# F405ADC_plata.net
KiCad netlist of a schematic drawn in Altium Designer
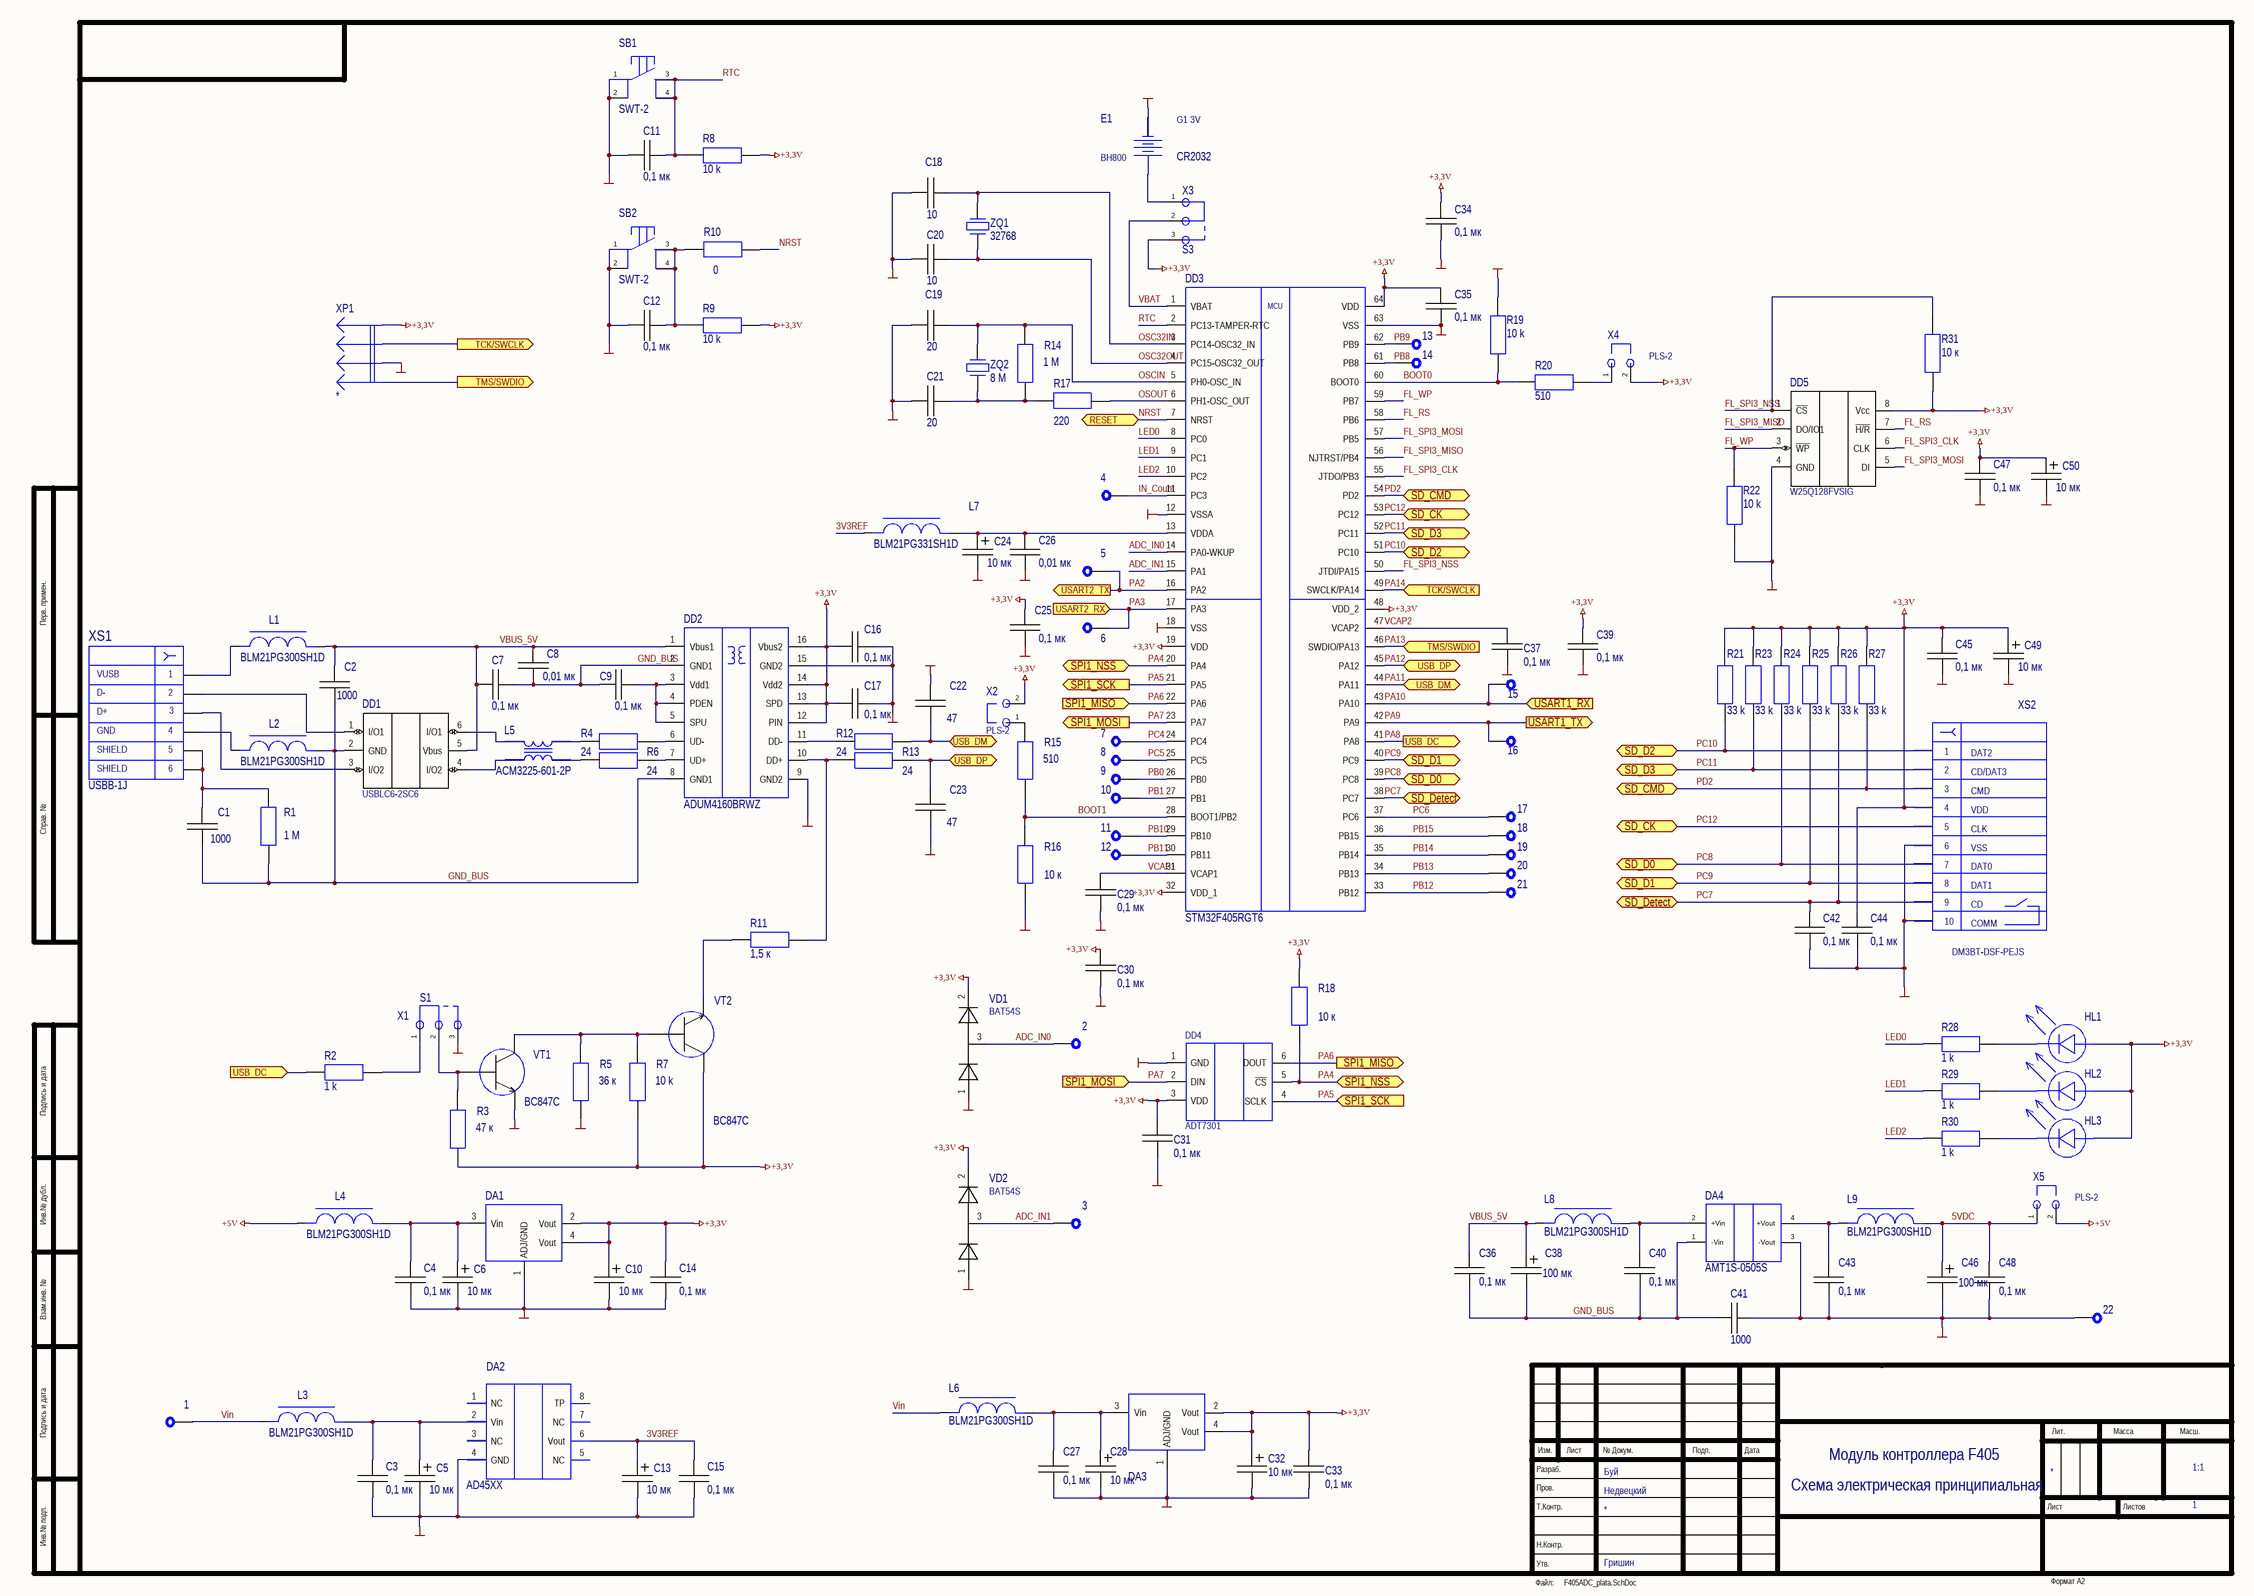
[diagram p0: F405ADC_plata.SchDoc]

(export (version "E")
  (design (tool "Eeschema 10.0.6"))
  (components
    (comp (ref "1")
      (value "PIN")
      (footprint "Hole")
      (description "PIN, hole")
      (libsource (lib "Connectors") (part "PIN"))
    )
    (comp (ref "2")
      (value "PIN")
      (footprint "Hole")
      (description "PIN, hole")
      (libsource (lib "Connectors") (part "PIN"))
    )
    (comp (ref "3")
      (value "PIN")
      (footprint "Hole")
      (description "PIN, hole")
      (libsource (lib "Connectors") (part "PIN"))
    )
    (comp (ref "4")
      (value "PIN")
      (footprint "Hole")
      (description "PIN, hole")
      (libsource (lib "Connectors") (part "PIN"))
    )
    (comp (ref "5")
      (value "PIN")
      (footprint "Hole")
      (description "PIN, hole")
      (libsource (lib "Connectors") (part "PIN"))
    )
    (comp (ref "6")
      (value "PIN")
      (footprint "Hole")
      (description "PIN, hole")
      (libsource (lib "Connectors") (part "PIN"))
    )
    (comp (ref "7")
      (value "PIN")
      (footprint "Hole")
      (description "PIN, hole")
      (libsource (lib "Connectors") (part "PIN"))
    )
    (comp (ref "8")
      (value "PIN")
      (footprint "Hole")
      (description "PIN, hole")
      (libsource (lib "Connectors") (part "PIN"))
    )
    (comp (ref "9")
      (value "PIN")
      (footprint "Hole")
      (description "PIN, hole")
      (libsource (lib "Connectors") (part "PIN"))
    )
    (comp (ref "10")
      (value "PIN")
      (footprint "Hole")
      (description "PIN, hole")
      (libsource (lib "Connectors") (part "PIN"))
    )
    (comp (ref "11")
      (value "PIN")
      (footprint "Hole")
      (description "PIN, hole")
      (libsource (lib "Connectors") (part "PIN"))
    )
    (comp (ref "12")
      (value "PIN")
      (footprint "Hole")
      (description "PIN, hole")
      (libsource (lib "Connectors") (part "PIN"))
    )
    (comp (ref "13")
      (value "PIN")
      (footprint "Hole")
      (description "PIN, hole")
      (libsource (lib "Connectors") (part "PIN"))
    )
    (comp (ref "14")
      (value "PIN")
      (footprint "Hole")
      (description "PIN, hole")
      (libsource (lib "Connectors") (part "PIN"))
    )
    (comp (ref "15")
      (value "PIN")
      (footprint "Hole")
      (description "PIN, hole")
      (libsource (lib "Connectors") (part "PIN"))
    )
    (comp (ref "16")
      (value "PIN")
      (footprint "Hole")
      (description "PIN, hole")
      (libsource (lib "Connectors") (part "PIN"))
    )
    (comp (ref "17")
      (value "PIN")
      (footprint "Hole")
      (description "PIN, hole")
      (libsource (lib "Connectors") (part "PIN"))
    )
    (comp (ref "18")
      (value "PIN")
      (footprint "Hole")
      (description "PIN, hole")
      (libsource (lib "Connectors") (part "PIN"))
    )
    (comp (ref "19")
      (value "PIN")
      (footprint "Hole")
      (description "PIN, hole")
      (libsource (lib "Connectors") (part "PIN"))
    )
    (comp (ref "20")
      (value "PIN")
      (footprint "Hole")
      (description "PIN, hole")
      (libsource (lib "Connectors") (part "PIN"))
    )
    (comp (ref "21")
      (value "PIN")
      (footprint "Hole")
      (description "PIN, hole")
      (libsource (lib "Connectors") (part "PIN"))
    )
    (comp (ref "22")
      (value "PIN")
      (footprint "Hole")
      (description "PIN, hole")
      (libsource (lib "Connectors") (part "PIN"))
    )
    (comp (ref "C1")
      (value "1000")
      (footprint "C0805")
      (description "Capasitor")
      (fields (field (name "PART NUMBER") "C"))
      (libsource (lib "RLC_GOST") (part "C"))
    )
    (comp (ref "C2")
      (value "1000")
      (footprint "C0805")
      (description "Capasitor")
      (libsource (lib "RLC_GOST") (part "C"))
    )
    (comp (ref "C3")
      (value "0,1 мк")
      (footprint "C0805")
      (description "Capasitor")
      (fields (field (name "PART NUMBER") "C"))
      (libsource (lib "RLC_GOST") (part "C"))
    )
    (comp (ref "C4")
      (value "0,1 мк")
      (footprint "C0805")
      (description "Capasitor")
      (fields (field (name "PART NUMBER") "C"))
      (libsource (lib "RLC_GOST") (part "C"))
    )
    (comp (ref "C5")
      (value "10 мк")
      (footprint "3216")
      (description "Capasitor_polar")
      (fields (field (name "PART NUMBER") "CapPol"))
      (libsource (lib "RLC_GOST") (part "CapPol"))
    )
    (comp (ref "C6")
      (value "10 мк")
      (footprint "3216")
      (description "Capasitor_polar")
      (fields (field (name "PART NUMBER") "CapPol"))
      (libsource (lib "RLC_GOST") (part "CapPol"))
    )
    (comp (ref "C7")
      (value "0,1 мк")
      (footprint "C0805")
      (description "Capasitor")
      (fields (field (name "PART NUMBER") "C"))
      (libsource (lib "RLC_GOST") (part "C"))
    )
    (comp (ref "C8")
      (value "0,01 мк")
      (footprint "C0805")
      (description "Capasitor")
      (fields (field (name "PART NUMBER") "C"))
      (libsource (lib "RLC_GOST") (part "C"))
    )
    (comp (ref "C9")
      (value "0,1 мк")
      (footprint "C0805")
      (description "Capasitor")
      (fields (field (name "PART NUMBER") "C"))
      (libsource (lib "RLC_GOST") (part "C"))
    )
    (comp (ref "C10")
      (value "10 мк")
      (footprint "3216")
      (description "Capasitor_polar")
      (fields (field (name "PART NUMBER") "CapPol"))
      (libsource (lib "RLC_GOST") (part "CapPol"))
    )
    (comp (ref "C11")
      (value "0,1 мк")
      (footprint "C0805")
      (description "Capasitor")
      (libsource (lib "RLC_GOST") (part "C"))
    )
    (comp (ref "C12")
      (value "0,1 мк")
      (footprint "C0805")
      (description "Capasitor")
      (libsource (lib "RLC_GOST") (part "C"))
    )
    (comp (ref "C13")
      (value "10 мк")
      (footprint "3216")
      (description "Capasitor_polar")
      (fields (field (name "PART NUMBER") "CapPol"))
      (libsource (lib "RLC_GOST") (part "CapPol"))
    )
    (comp (ref "C14")
      (value "0,1 мк")
      (footprint "C0805")
      (description "Capasitor")
      (fields (field (name "PART NUMBER") "C"))
      (libsource (lib "RLC_GOST") (part "C"))
    )
    (comp (ref "C15")
      (value "0,1 мк")
      (footprint "C0805")
      (description "Capasitor")
      (fields (field (name "PART NUMBER") "C"))
      (libsource (lib "RLC_GOST") (part "C"))
    )
    (comp (ref "C16")
      (value "0,1 мк")
      (footprint "C0805")
      (description "Capasitor")
      (fields (field (name "PART NUMBER") "C"))
      (libsource (lib "RLC_GOST") (part "C"))
    )
    (comp (ref "C17")
      (value "0,1 мк")
      (footprint "C0805")
      (description "Capasitor")
      (fields (field (name "PART NUMBER") "C"))
      (libsource (lib "RLC_GOST") (part "C"))
    )
    (comp (ref "C18")
      (value "10")
      (footprint "CAPC1608X05N")
      (description "Capasitor")
      (libsource (lib "RLC_GOST") (part "C"))
    )
    (comp (ref "C19")
      (value "20")
      (footprint "CAPC1608X05N")
      (description "Capasitor")
      (libsource (lib "RLC_GOST") (part "C"))
    )
    (comp (ref "C20")
      (value "10")
      (footprint "CAPC1608X05N")
      (description "Capasitor")
      (libsource (lib "RLC_GOST") (part "C"))
    )
    (comp (ref "C21")
      (value "20")
      (footprint "CAPC1608X05N")
      (description "Capasitor")
      (libsource (lib "RLC_GOST") (part "C"))
    )
    (comp (ref "C22")
      (value "47")
      (footprint "C0805")
      (description "Capasitor")
      (fields (field (name "PART NUMBER") "C"))
      (libsource (lib "RLC_GOST") (part "C"))
    )
    (comp (ref "C23")
      (value "47")
      (footprint "C0805")
      (description "Capasitor")
      (fields (field (name "PART NUMBER") "C"))
      (libsource (lib "RLC_GOST") (part "C"))
    )
    (comp (ref "C24")
      (value "10 мк")
      (footprint "3216")
      (description "Capasitor_polar")
      (fields (field (name "PART NUMBER") "CapPol"))
      (libsource (lib "RLC_GOST") (part "CapPol"))
    )
    (comp (ref "C25")
      (value "0,1 мк")
      (footprint "C0805")
      (description "Capasitor")
      (fields (field (name "PART NUMBER") "C"))
      (libsource (lib "RLC_GOST") (part "C"))
    )
    (comp (ref "C26")
      (value "0,01 мк")
      (footprint "C0805")
      (description "Capasitor")
      (fields (field (name "PART NUMBER") "C"))
      (libsource (lib "RLC_GOST") (part "C"))
    )
    (comp (ref "C27")
      (value "0,1 мк")
      (footprint "C0805")
      (description "Capasitor")
      (fields (field (name "PART NUMBER") "C"))
      (libsource (lib "RLC_GOST") (part "C"))
    )
    (comp (ref "C28")
      (value "10 мк")
      (footprint "3216")
      (description "Capasitor_polar")
      (fields (field (name "PART NUMBER") "CapPol"))
      (libsource (lib "RLC_GOST") (part "CapPol"))
    )
    (comp (ref "C29")
      (value "0,1 мк")
      (footprint "C0805")
      (description "Capasitor")
      (fields (field (name "PART NUMBER") "C"))
      (libsource (lib "RLC_GOST") (part "C"))
    )
    (comp (ref "C30")
      (value "0,1 мк")
      (footprint "C0805")
      (description "Capasitor")
      (fields (field (name "PART NUMBER") "C"))
      (libsource (lib "RLC_GOST") (part "C"))
    )
    (comp (ref "C31")
      (value "0,1 мк")
      (footprint "C0805")
      (description "Capasitor")
      (fields (field (name "PART NUMBER") "C"))
      (libsource (lib "RLC_GOST") (part "C"))
    )
    (comp (ref "C32")
      (value "10 мк")
      (footprint "3216")
      (description "Capasitor_polar")
      (fields (field (name "PART NUMBER") "CapPol"))
      (libsource (lib "RLC_GOST") (part "CapPol"))
    )
    (comp (ref "C33")
      (value "0,1 мк")
      (footprint "C0805")
      (description "Capasitor")
      (fields (field (name "PART NUMBER") "C"))
      (libsource (lib "RLC_GOST") (part "C"))
    )
    (comp (ref "C34")
      (value "0,1 мк")
      (footprint "C0805")
      (description "Capasitor")
      (fields (field (name "PART NUMBER") "C"))
      (libsource (lib "RLC_GOST") (part "C"))
    )
    (comp (ref "C35")
      (value "0,1 мк")
      (footprint "C0805")
      (description "Capasitor")
      (fields (field (name "PART NUMBER") "C"))
      (libsource (lib "RLC_GOST") (part "C"))
    )
    (comp (ref "C36")
      (value "0,1 мк")
      (footprint "C0805")
      (description "Capasitor")
      (fields (field (name "PART NUMBER") "C"))
      (libsource (lib "RLC_GOST") (part "C"))
    )
    (comp (ref "C37")
      (value "0,1 мк")
      (footprint "RC0805-2.2")
      (description "Capasitor")
      (fields (field (name "PART NUMBER") "C"))
      (libsource (lib "RLC_GOST") (part "C"))
    )
    (comp (ref "C38")
      (value "100 мк")
      (footprint "X-7343-43")
      (description "Capasitor_polar")
      (libsource (lib "") (part "CapPol_1"))
    )
    (comp (ref "C39")
      (value "0,1 мк")
      (footprint "C0805")
      (description "Capasitor")
      (fields (field (name "PART NUMBER") "C"))
      (libsource (lib "RLC_GOST") (part "C"))
    )
    (comp (ref "C40")
      (value "0,1 мк")
      (footprint "C0805")
      (description "Capasitor")
      (fields (field (name "PART NUMBER") "C"))
      (libsource (lib "RLC_GOST") (part "C"))
    )
    (comp (ref "C41")
      (value "1000")
      (footprint "KVR")
      (description "Capasitor")
      (libsource (lib "RLC_GOST") (part "C"))
    )
    (comp (ref "C42")
      (value "0,1 мк")
      (footprint "C0805")
      (description "Capasitor")
      (fields (field (name "PART NUMBER") "C"))
      (libsource (lib "RLC_GOST") (part "C"))
    )
    (comp (ref "C43")
      (value "0,1 мк")
      (footprint "C0805")
      (description "Capasitor")
      (fields (field (name "PART NUMBER") "C"))
      (libsource (lib "RLC_GOST") (part "C"))
    )
    (comp (ref "C44")
      (value "0,1 мк")
      (footprint "C0805")
      (description "Capasitor")
      (fields (field (name "PART NUMBER") "C"))
      (libsource (lib "RLC_GOST") (part "C"))
    )
    (comp (ref "C45")
      (value "0,1 мк")
      (footprint "C0805")
      (description "Capasitor")
      (fields (field (name "PART NUMBER") "C"))
      (libsource (lib "RLC_GOST") (part "C"))
    )
    (comp (ref "C46")
      (value "100 мк")
      (footprint "X-7343-43")
      (description "Capasitor_polar")
      (libsource (lib "") (part "CapPol_1"))
    )
    (comp (ref "C47")
      (value "0,1 мк")
      (footprint "C0805")
      (description "Capasitor")
      (fields (field (name "PART NUMBER") "C"))
      (libsource (lib "RLC_GOST") (part "C"))
    )
    (comp (ref "C48")
      (value "0,1 мк")
      (footprint "C0805")
      (description "Capasitor")
      (fields (field (name "PART NUMBER") "C"))
      (libsource (lib "RLC_GOST") (part "C"))
    )
    (comp (ref "C49")
      (value "10 мк")
      (footprint "3216")
      (description "Capasitor_polar")
      (fields (field (name "PART NUMBER") "CapPol"))
      (libsource (lib "RLC_GOST") (part "CapPol"))
    )
    (comp (ref "C50")
      (value "10 мк")
      (footprint "3216")
      (description "Capasitor_polar")
      (fields (field (name "PART NUMBER") "CapPol"))
      (libsource (lib "RLC_GOST") (part "CapPol"))
    )
    (comp (ref "DA1")
      (value "LM1117")
      (footprint "SOT223")
      (description "Positive voltage regulators")
      (fields (field (name "MANUFACTURER") "National Semiconductor"))
      (libsource (lib "Stabil") (part "LM1117"))
    )
    (comp (ref "DA2")
      (value "AD45XX")
      (footprint "SO8")
      (description "Ultralow Noise, High Accuracy  Voltage References")
      (fields (field (name "MANUFACTURER") "Analog Devices"))
      (libsource (lib "REF") (part "AD45XX"))
    )
    (comp (ref "DA3")
      (value "LM1117")
      (footprint "SOT223")
      (description "Positive voltage regulators")
      (fields (field (name "MANUFACTURER") "National Semiconductor"))
      (libsource (lib "Stabil") (part "LM1117"))
    )
    (comp (ref "DA4")
      (value "AMT1S-0505S")
      (footprint "HOLE_4")
      (libsource (lib "ConverterDC") (part "AMT1S-0505S"))
    )
    (comp (ref "DD1")
      (value "USBLC6-2SC6")
      (footprint "SOT23-6L")
      (description "ESD PROTECTION")
      (fields (field (name "MANUFACTURER") "STMicroelectronics"))
      (libsource (lib "Diod") (part "USBLC6"))
    )
    (comp (ref "DD2")
      (value "ADUM4160BRWZ")
      (footprint "RW-16")
      (libsource (lib "IsolatedCircuit") (part "ADUM4160"))
    )
    (comp (ref "DD3")
      (value "STM32F405RGT6")
      (footprint "LQFP64_M")
      (libsource (lib "STM32") (part "STM32F405RGT6"))
    )
    (comp (ref "DD4")
      (value "ADT7301")
      (footprint "SOT23-6")
      (description "Temperature sensor")
      (libsource (lib "temp_sensor") (part "ADT7301"))
    )
    (comp (ref "DD5")
      (value "W25Q128FVSIG")
      (footprint "SOIC127P790X100-8N")
      (description "Flash")
      (libsource (lib "Communication transceiver") (part "W25Q128FVSIG"))
    )
    (comp (ref "E1")
      (value "BH800")
      (footprint "BATTERY_20mm")
      (fields (field (name "ALTIUM_VALUE") "CR2032") (field (name "G") "G1 3V"))
      (libsource (lib "Connectors") (part "BH800"))
    )
    (comp (ref "HL1")
      (value "REC-T1608UYC-B1-6")
      (footprint "C0805")
      (description "HL")
      (libsource (lib "Diodes") (part "HLSMD"))
    )
    (comp (ref "HL2")
      (value "REC-T1608UYC-B1-6")
      (footprint "C0805")
      (description "HL")
      (libsource (lib "Diodes") (part "HLSMD"))
    )
    (comp (ref "HL3")
      (value "REC-T1608UYC-B1-6")
      (footprint "C0805")
      (description "HL")
      (libsource (lib "Diodes") (part "HLSMD"))
    )
    (comp (ref "L1")
      (value "BLM21PG300SH1D")
      (footprint "C0805")
      (description "Ferrite bead")
      (libsource (lib "RLC_GOST") (part "B"))
    )
    (comp (ref "L2")
      (value "BLM21PG300SH1D")
      (footprint "C0805")
      (description "Ferrite bead")
      (libsource (lib "RLC_GOST") (part "B"))
    )
    (comp (ref "L3")
      (value "BLM21PG300SH1D")
      (footprint "C0805")
      (description "Ferrite bead")
      (libsource (lib "RLC_GOST") (part "B"))
    )
    (comp (ref "L4")
      (value "BLM21PG300SH1D")
      (footprint "C0805")
      (description "Ferrite bead")
      (libsource (lib "RLC_GOST") (part "B"))
    )
    (comp (ref "L5")
      (value "ACM3225-601-2P")
      (footprint "ACM3225")
      (libsource (lib "RLC_GOST") (part "ACM3225-601-2P"))
    )
    (comp (ref "L6")
      (value "BLM21PG300SH1D")
      (footprint "C0805")
      (description "Ferrite bead")
      (libsource (lib "RLC_GOST") (part "B"))
    )
    (comp (ref "L7")
      (value "BLM21PG331SH1D")
      (footprint "C0805")
      (description "Ferrite bead")
      (libsource (lib "RLC_GOST") (part "B"))
    )
    (comp (ref "L8")
      (value "BLM21PG300SH1D")
      (footprint "C0805")
      (description "Ferrite bead")
      (libsource (lib "RLC_GOST") (part "B"))
    )
    (comp (ref "L9")
      (value "BLM21PG300SH1D")
      (footprint "C0805")
      (description "Ferrite bead")
      (libsource (lib "RLC_GOST") (part "B"))
    )
    (comp (ref "R1")
      (value "1 M")
      (footprint "RC0805-2")
      (description "Resistor,2 Pin")
      (libsource (lib "RLC_GOST") (part "R_Gost"))
    )
    (comp (ref "R2")
      (value "1 k")
      (footprint "RC0805-2")
      (description "Resistor,2 Pin")
      (libsource (lib "RLC_GOST") (part "R_Gost"))
    )
    (comp (ref "R3")
      (value "47 к")
      (footprint "RC0805-2")
      (description "Resistor,2 Pin")
      (libsource (lib "RLC_GOST") (part "R_Gost"))
    )
    (comp (ref "R4")
      (value "24")
      (footprint "RC0805-2")
      (description "Resistor,2 Pin")
      (libsource (lib "RLC_GOST") (part "R_Gost"))
    )
    (comp (ref "R5")
      (value "36 к")
      (footprint "RC0805-2")
      (description "Resistor,2 Pin")
      (libsource (lib "RLC_GOST") (part "R_Gost"))
    )
    (comp (ref "R6")
      (value "24")
      (footprint "RC0805-2")
      (description "Resistor,2 Pin")
      (libsource (lib "RLC_GOST") (part "R_Gost"))
    )
    (comp (ref "R7")
      (value "10 k")
      (footprint "RC0805-2")
      (description "Resistor,2 Pin")
      (libsource (lib "RLC_GOST") (part "R_Gost"))
    )
    (comp (ref "R8")
      (value "10 k")
      (footprint "RC0805-2")
      (description "Resistor,2 Pin")
      (libsource (lib "RLC_GOST") (part "R_Gost"))
    )
    (comp (ref "R9")
      (value "10 k")
      (footprint "RC0805-2")
      (description "Resistor,2 Pin")
      (libsource (lib "RLC_GOST") (part "R_Gost"))
    )
    (comp (ref "R10")
      (value "0")
      (footprint "RC0805-2")
      (description "Resistor,2 Pin")
      (libsource (lib "RLC_GOST") (part "R_Gost"))
    )
    (comp (ref "R11")
      (value "1,5 к")
      (footprint "RC0805-2")
      (description "Resistor,2 Pin")
      (libsource (lib "RLC_GOST") (part "R_Gost"))
    )
    (comp (ref "R12")
      (value "24")
      (footprint "RC0805-2")
      (description "Resistor,2 Pin")
      (libsource (lib "RLC_GOST") (part "R_Gost"))
    )
    (comp (ref "R13")
      (value "24")
      (footprint "RC0805-2")
      (description "Resistor,2 Pin")
      (libsource (lib "RLC_GOST") (part "R_Gost"))
    )
    (comp (ref "R14")
      (value "1 М")
      (footprint "CAPC1608X05N")
      (description "Resistor,2 Pin")
      (libsource (lib "RLC_GOST") (part "R_Gost"))
    )
    (comp (ref "R15")
      (value "510")
      (footprint "RC0805-2")
      (description "Resistor,2 Pin")
      (libsource (lib "RLC_GOST") (part "R_Gost"))
    )
    (comp (ref "R16")
      (value "10 к")
      (footprint "RC0805-2")
      (description "Resistor,2 Pin")
      (libsource (lib "RLC_GOST") (part "R_Gost"))
    )
    (comp (ref "R17")
      (value "220")
      (footprint "CAPC1608X05N")
      (description "Resistor,2 Pin")
      (libsource (lib "RLC_GOST") (part "R_Gost"))
    )
    (comp (ref "R18")
      (value "10 к")
      (footprint "RC0805-2")
      (description "Resistor,2 Pin")
      (libsource (lib "RLC_GOST") (part "R_Gost"))
    )
    (comp (ref "R19")
      (value "10 k")
      (footprint "RC0805-2.2")
      (description "Resistor,2 Pin")
      (libsource (lib "RLC_GOST") (part "R_Gost"))
    )
    (comp (ref "R20")
      (value "510")
      (footprint "RC0805-2.2")
      (description "Resistor,2 Pin")
      (libsource (lib "RLC_GOST") (part "R_Gost"))
    )
    (comp (ref "R21")
      (value "33 k")
      (footprint "RC0805-2")
      (description "Resistor,2 Pin")
      (libsource (lib "RLC_GOST") (part "R_Gost"))
    )
    (comp (ref "R22")
      (value "10 k")
      (footprint "RC0805-2")
      (description "Resistor,2 Pin")
      (libsource (lib "RLC_GOST") (part "R_Gost"))
    )
    (comp (ref "R23")
      (value "33 k")
      (footprint "RC0805-2")
      (description "Resistor,2 Pin")
      (libsource (lib "RLC_GOST") (part "R_Gost"))
    )
    (comp (ref "R24")
      (value "33 k")
      (footprint "RC0805-2")
      (description "Resistor,2 Pin")
      (libsource (lib "RLC_GOST") (part "R_Gost"))
    )
    (comp (ref "R25")
      (value "33 k")
      (footprint "RC0805-2")
      (description "Resistor,2 Pin")
      (libsource (lib "RLC_GOST") (part "R_Gost"))
    )
    (comp (ref "R26")
      (value "33 k")
      (footprint "RC0805-2")
      (description "Resistor,2 Pin")
      (libsource (lib "RLC_GOST") (part "R_Gost"))
    )
    (comp (ref "R27")
      (value "33 k")
      (footprint "RC0805-2")
      (description "Resistor,2 Pin")
      (libsource (lib "RLC_GOST") (part "R_Gost"))
    )
    (comp (ref "R28")
      (value "1 k")
      (footprint "RC0805-2")
      (description "Resistor,2 Pin")
      (libsource (lib "RLC_GOST") (part "R_Gost"))
    )
    (comp (ref "R29")
      (value "1 k")
      (footprint "RC0805-2")
      (description "Resistor,2 Pin")
      (libsource (lib "RLC_GOST") (part "R_Gost"))
    )
    (comp (ref "R30")
      (value "1 k")
      (footprint "RC0805-2")
      (description "Resistor,2 Pin")
      (libsource (lib "RLC_GOST") (part "R_Gost"))
    )
    (comp (ref "R31")
      (value "10 к")
      (footprint "RC0805-2")
      (description "Resistor,2 Pin")
      (libsource (lib "RLC_GOST") (part "R_Gost"))
    )
    (comp (ref "SB1")
      (value "SWT-2")
      (footprint "SWT2")
      (description "SWT-2, key")
      (libsource (lib "Keys") (part "SWT-2"))
    )
    (comp (ref "SB2")
      (value "SWT-2")
      (footprint "SWT2")
      (description "SWT-2, key")
      (libsource (lib "Keys") (part "SWT-2"))
    )
    (comp (ref "VD1")
      (value "BAT54S")
      (footprint "SOT23")
      (description "Diod Schottky, 3 pin")
      (fields (field (name "MANUFACTURER") "Fairchild"))
      (libsource (lib "Diod") (part "BS40-04"))
    )
    (comp (ref "VD2")
      (value "BAT54S")
      (footprint "SOT23")
      (description "Diod Schottky, 3 pin")
      (fields (field (name "MANUFACTURER") "Fairchild"))
      (libsource (lib "Diod") (part "BS40-04"))
    )
    (comp (ref "VT1")
      (value "BC847C")
      (footprint "SOT23")
      (description "Transistor NPN Generic")
      (libsource (lib "Transistor") (part "BC846"))
    )
    (comp (ref "VT2")
      (value "BC847C")
      (footprint "SOT23")
      (description "Transistor NPN Generic")
      (libsource (lib "Transistor") (part "BC846"))
    )
    (comp (ref "X1")
      (value "PLS-03")
      (footprint "PLS-3")
      (fields (field (name "JAMPER") "S1"))
      (libsource (lib "Connectors") (part "J3"))
    )
    (comp (ref "X2")
      (value "PLS-2")
      (footprint "PLS-2")
      (description "PLS-02")
      (fields (field (name "MANUFACTURER") "Ningbo"))
      (libsource (lib "Connectors") (part "J2"))
    )
    (comp (ref "X3")
      (value "PLS-03")
      (footprint "PLS-3")
      (fields (field (name "JAMPER") "S3"))
      (libsource (lib "Connectors") (part "J3"))
    )
    (comp (ref "X4")
      (value "PLS-2")
      (footprint "PLS-2")
      (description "PLS-02")
      (fields (field (name "MANUFACTURER") "Ningbo"))
      (libsource (lib "Connectors") (part "J2"))
    )
    (comp (ref "X5")
      (value "PLS-2")
      (footprint "PLS-2")
      (description "PLS-02")
      (fields (field (name "MANUFACTURER") "Ningbo"))
      (libsource (lib "Connectors") (part "J2"))
    )
    (comp (ref "XP1")
      (value "*")
      (footprint "PLS-4")
      (description "XP4")
      (libsource (lib "Connectors") (part "XP4"))
    )
    (comp (ref "XS1") (value "USBB-1J") (footprint "USBB-1J") (libsource (lib "Connectors") (part "USBB-1J")))
    (comp (ref "XS2")
      (value "DM3BT-DSF-PEJS")
      (footprint "112J-TDAR-R")
      (description "SD-card socket")
      (fields (field (name "MANUFACTURER") "Hirose"))
      (libsource (lib "Connectors") (part "MicroSD"))
    )
    (comp (ref "ZQ1")
      (value "32768")
      (footprint "KX–327NHT")
      (description "OSC")
      (fields (field (name "COMPONENTLINK1URL") "D:\\datasheet\\Кварцы\\00688.pdf"))
      (libsource (lib "Resonators") (part "OSC"))
    )
    (comp (ref "ZQ2")
      (value "8 М")
      (footprint "HC-49U_5mm")
      (description "OSC")
      (fields (field (name "COMPONENTLINK1URL") "D:\\datasheet\\Кварцы\\00688.pdf"))
      (libsource (lib "Resonators") (part "OSC"))
    )
  )
  (nets
    (net (code "1") (name "+3,3V") (class "Default")
      (node (ref "C10") (pin "1") (pinfunction "+_1") (pintype "passive"))
      (node (ref "C14") (pin "1") (pinfunction "1_1") (pintype "passive"))
      (node (ref "C16") (pin "1") (pinfunction "1_1") (pintype "passive"))
      (node (ref "C17") (pin "1") (pinfunction "1_1") (pintype "passive"))
      (node (ref "C25") (pin "1") (pinfunction "1_1") (pintype "passive"))
      (node (ref "C30") (pin "1") (pinfunction "1_1") (pintype "passive"))
      (node (ref "C31") (pin "1") (pinfunction "1_1") (pintype "passive"))
      (node (ref "C32") (pin "1") (pinfunction "+_1") (pintype "passive"))
      (node (ref "C33") (pin "1") (pinfunction "1_1") (pintype "passive"))
      (node (ref "C34") (pin "1") (pinfunction "1_1") (pintype "passive"))
      (node (ref "C35") (pin "1") (pinfunction "1_1") (pintype "passive"))
      (node (ref "C39") (pin "1") (pinfunction "1_1") (pintype "passive"))
      (node (ref "C44") (pin "1") (pinfunction "1_1") (pintype "passive"))
      (node (ref "C45") (pin "1") (pinfunction "1_1") (pintype "passive"))
      (node (ref "C47") (pin "1") (pinfunction "1_1") (pintype "passive"))
      (node (ref "C49") (pin "1") (pinfunction "+_1") (pintype "passive"))
      (node (ref "C50") (pin "1") (pinfunction "+_1") (pintype "passive"))
      (node (ref "DA1") (pin "2") (pinfunction "Vout_2") (pintype "power_in"))
      (node (ref "DA1") (pin "4") (pinfunction "Vout_4") (pintype "passive"))
      (node (ref "DA3") (pin "2") (pinfunction "Vout_2") (pintype "power_in"))
      (node (ref "DA3") (pin "4") (pinfunction "Vout_4") (pintype "passive"))
      (node (ref "DD2") (pin "12") (pinfunction "PIN_12") (pintype "passive"))
      (node (ref "DD2") (pin "13") (pinfunction "SPD_13") (pintype "passive"))
      (node (ref "DD2") (pin "14") (pinfunction "Vdd2_14") (pintype "passive"))
      (node (ref "DD2") (pin "16") (pinfunction "Vbus2_16") (pintype "passive"))
      (node (ref "DD3") (pin "19") (pinfunction "VDD_19") (pintype "passive"))
      (node (ref "DD3") (pin "32") (pinfunction "VDD_1_32") (pintype "passive"))
      (node (ref "DD3") (pin "48") (pinfunction "VDD_2_48") (pintype "passive"))
      (node (ref "DD3") (pin "64") (pinfunction "VDD_64") (pintype "passive"))
      (node (ref "DD4") (pin "3") (pinfunction "VDD_3") (pintype "passive"))
      (node (ref "DD5") (pin "8") (pinfunction "Vcc_8") (pintype "passive"))
      (node (ref "HL1") (pin "1") (pinfunction "+_1") (pintype "passive"))
      (node (ref "HL2") (pin "1") (pinfunction "+_1") (pintype "passive"))
      (node (ref "HL3") (pin "1") (pinfunction "+_1") (pintype "passive"))
      (node (ref "R18") (pin "1") (pinfunction "1_1") (pintype "passive"))
      (node (ref "R21") (pin "1") (pinfunction "1_1") (pintype "passive"))
      (node (ref "R23") (pin "1") (pinfunction "1_1") (pintype "passive"))
      (node (ref "R24") (pin "1") (pinfunction "1_1") (pintype "passive"))
      (node (ref "R25") (pin "1") (pinfunction "1_1") (pintype "passive"))
      (node (ref "R26") (pin "1") (pinfunction "1_1") (pintype "passive"))
      (node (ref "R27") (pin "1") (pinfunction "1_1") (pintype "passive"))
      (node (ref "R3") (pin "2") (pinfunction "2_2") (pintype "passive"))
      (node (ref "R31") (pin "1") (pinfunction "1_1") (pintype "passive"))
      (node (ref "R7") (pin "2") (pinfunction "2_2") (pintype "passive"))
      (node (ref "R8") (pin "2") (pinfunction "2_2") (pintype "passive"))
      (node (ref "R9") (pin "2") (pinfunction "2_2") (pintype "passive"))
      (node (ref "VD1") (pin "2") (pinfunction "-_2") (pintype "passive"))
      (node (ref "VD2") (pin "2") (pinfunction "-_2") (pintype "passive"))
      (node (ref "VT2") (pin "3") (pinfunction "K_3") (pintype "passive"))
      (node (ref "X2") (pin "2") (pinfunction "2_2") (pintype "passive"))
      (node (ref "X3") (pin "3") (pinfunction "3_3") (pintype "passive"))
      (node (ref "X4") (pin "2") (pinfunction "2_2") (pintype "passive"))
      (node (ref "XP1") (pin "1") (pinfunction "1_1") (pintype "passive"))
      (node (ref "XS2") (pin "4") (pinfunction "4_4") (pintype "passive"))
    )
    (net (code "2") (name "+5V") (class "Default")
      (node (ref "L4") (pin "1") (pinfunction "1_1") (pintype "passive"))
      (node (ref "X5") (pin "2") (pinfunction "2_2") (pintype "passive"))
    )
    (net (code "3") (name "/3V3REF") (class "Default")
      (node (ref "C13") (pin "1") (pinfunction "+_1") (pintype "passive"))
      (node (ref "C15") (pin "1") (pinfunction "1_1") (pintype "passive"))
      (node (ref "DA2") (pin "6") (pinfunction "Vout_6") (pintype "passive"))
      (node (ref "L7") (pin "1") (pinfunction "1_1") (pintype "passive"))
    )
    (net (code "4") (name "/5VDC") (class "Default")
      (node (ref "C46") (pin "1") (pinfunction "1_1") (pintype "passive"))
      (node (ref "C48") (pin "1") (pinfunction "1_1") (pintype "passive"))
      (node (ref "L9") (pin "2") (pinfunction "2_2") (pintype "passive"))
      (node (ref "X5") (pin "1") (pinfunction "1_1") (pintype "passive"))
    )
    (net (code "5") (name "/ADC_IN0") (class "Default")
      (node (ref "2") (pin "1") (pinfunction "1_1") (pintype "passive"))
      (node (ref "DD3") (pin "14") (pinfunction "PA0-WKUP_14") (pintype "passive"))
      (node (ref "VD1") (pin "3") (pintype "passive"))
    )
    (net (code "6") (name "/ADC_IN1") (class "Default")
      (node (ref "3") (pin "1") (pinfunction "1_1") (pintype "passive"))
      (node (ref "DD3") (pin "15") (pinfunction "PA1_15") (pintype "passive"))
      (node (ref "VD2") (pin "3") (pintype "passive"))
    )
    (net (code "7") (name "/BOOT0") (class "Default")
      (node (ref "DD3") (pin "60") (pinfunction "BOOT0_60") (pintype "passive"))
      (node (ref "R19") (pin "2") (pinfunction "2_2") (pintype "passive"))
      (node (ref "R20") (pin "1") (pinfunction "1_1") (pintype "passive"))
    )
    (net (code "8") (name "/BOOT1") (class "Default")
      (node (ref "DD3") (pin "28") (pinfunction "BOOT1/PB2_28") (pintype "passive"))
      (node (ref "R15") (pin "2") (pinfunction "2_2") (pintype "passive"))
      (node (ref "R16") (pin "1") (pinfunction "1_1") (pintype "passive"))
    )
    (net (code "9") (name "/FL_RS") (class "Default")
      (node (ref "DD3") (pin "58") (pinfunction "PB6_58") (pintype "passive"))
      (node (ref "DD5") (pin "7") (pinfunction "H/R_7") (pintype "passive"))
    )
    (net (code "10") (name "/FL_SPI3_CLK") (class "Default")
      (node (ref "DD3") (pin "55") (pinfunction "JTDO/PB3_55") (pintype "passive"))
      (node (ref "DD5") (pin "6") (pinfunction "CLK_6") (pintype "passive"))
    )
    (net (code "11") (name "/FL_SPI3_MISO") (class "Default")
      (node (ref "DD3") (pin "56") (pinfunction "NJTRST/PB4_56") (pintype "passive"))
      (node (ref "DD5") (pin "2") (pinfunction "DO/IO1_2") (pintype "passive"))
    )
    (net (code "12") (name "/FL_SPI3_MOSI") (class "Default")
      (node (ref "DD3") (pin "57") (pinfunction "PB5_57") (pintype "passive"))
      (node (ref "DD5") (pin "5") (pinfunction "DI_5") (pintype "passive"))
    )
    (net (code "13") (name "/FL_SPI3_NSS") (class "Default")
      (node (ref "DD3") (pin "50") (pinfunction "JTDI/PA15_50") (pintype "passive"))
      (node (ref "DD5") (pin "1") (pinfunction "CS_1") (pintype "passive"))
      (node (ref "R31") (pin "2") (pinfunction "2_2") (pintype "passive"))
    )
    (net (code "14") (name "/FL_WP") (class "Default")
      (node (ref "DD3") (pin "59") (pinfunction "PB7_59") (pintype "passive"))
      (node (ref "DD5") (pin "3") (pinfunction "WP_3") (pintype "bidirectional"))
      (node (ref "R22") (pin "1") (pinfunction "1_1") (pintype "passive"))
    )
    (net (code "15") (name "/GND_BUS") (class "Default")
      (node (ref "C1") (pin "1") (pinfunction "1_1") (pintype "passive"))
      (node (ref "C2") (pin "1") (pinfunction "1_1") (pintype "passive"))
      (node (ref "C36") (pin "2") (pinfunction "2_2") (pintype "passive"))
      (node (ref "C38") (pin "2") (pinfunction "2_2") (pintype "passive"))
      (node (ref "C40") (pin "2") (pinfunction "2_2") (pintype "passive"))
      (node (ref "C41") (pin "1") (pinfunction "1_1") (pintype "passive"))
      (node (ref "C7") (pin "2") (pinfunction "2_2") (pintype "passive"))
      (node (ref "C8") (pin "2") (pinfunction "2_2") (pintype "passive"))
      (node (ref "C9") (pin "1") (pinfunction "1_1") (pintype "passive"))
      (node (ref "DA4") (pin "1") (pinfunction "-Vin_1") (pintype "passive"))
      (node (ref "DD1") (pin "2") (pinfunction "GND_2") (pintype "power_in"))
      (node (ref "DD2") (pin "2") (pinfunction "GND1_2") (pintype "passive"))
      (node (ref "DD2") (pin "8") (pinfunction "GND1_8") (pintype "passive"))
      (node (ref "L2") (pin "2") (pinfunction "2_2") (pintype "passive"))
      (node (ref "R1") (pin "1") (pinfunction "1_1") (pintype "passive"))
    )
    (net (code "16") (name "/IN_Count") (class "Default")
      (node (ref "4") (pin "1") (pinfunction "1_1") (pintype "passive"))
      (node (ref "DD3") (pin "11") (pinfunction "PC3_11") (pintype "passive"))
    )
    (net (code "17") (name "/LED0") (class "Default")
      (node (ref "DD3") (pin "8") (pinfunction "PC0_8") (pintype "passive"))
      (node (ref "R28") (pin "1") (pinfunction "1_1") (pintype "passive"))
    )
    (net (code "18") (name "/LED1") (class "Default")
      (node (ref "DD3") (pin "9") (pinfunction "PC1_9") (pintype "passive"))
      (node (ref "R29") (pin "1") (pinfunction "1_1") (pintype "passive"))
    )
    (net (code "19") (name "/LED2") (class "Default")
      (node (ref "DD3") (pin "10") (pinfunction "PC2_10") (pintype "passive"))
      (node (ref "R30") (pin "1") (pinfunction "1_1") (pintype "passive"))
    )
    (net (code "20") (name "/NRST") (class "Default")
      (node (ref "DD3") (pin "7") (pinfunction "NRST_7") (pintype "passive"))
      (node (ref "R10") (pin "1") (pinfunction "1_1") (pintype "passive"))
    )
    (net (code "21") (name "/OSC32IN") (class "Default")
      (node (ref "C18") (pin "2") (pinfunction "2_2") (pintype "passive"))
      (node (ref "DD3") (pin "3") (pinfunction "PC14-OSC32_IN_3") (pintype "passive"))
      (node (ref "ZQ1") (pin "1") (pinfunction "1_1") (pintype "passive"))
    )
    (net (code "22") (name "/OSC32OUT") (class "Default")
      (node (ref "C20") (pin "2") (pinfunction "2_2") (pintype "passive"))
      (node (ref "DD3") (pin "4") (pinfunction "PC15-OSC32_OUT_4") (pintype "passive"))
      (node (ref "ZQ1") (pin "2") (pinfunction "2_2") (pintype "passive"))
    )
    (net (code "23") (name "/OSCIN") (class "Default")
      (node (ref "C19") (pin "2") (pinfunction "2_2") (pintype "passive"))
      (node (ref "DD3") (pin "5") (pinfunction "PH0-OSC_IN_5") (pintype "passive"))
      (node (ref "R14") (pin "1") (pinfunction "1_1") (pintype "passive"))
      (node (ref "ZQ2") (pin "2") (pinfunction "2_2") (pintype "passive"))
    )
    (net (code "24") (name "/OSOUT") (class "Default")
      (node (ref "DD3") (pin "6") (pinfunction "PH1-OSC_OUT_6") (pintype "passive"))
      (node (ref "R17") (pin "1") (pinfunction "1_1") (pintype "passive"))
    )
    (net (code "25") (name "/PA2") (class "Default")
      (node (ref "5") (pin "1") (pinfunction "1_1") (pintype "passive"))
      (node (ref "DD3") (pin "16") (pinfunction "PA2_16") (pintype "passive"))
    )
    (net (code "26") (name "/PA3") (class "Default")
      (node (ref "6") (pin "1") (pinfunction "1_1") (pintype "passive"))
      (node (ref "DD3") (pin "17") (pinfunction "PA3_17") (pintype "passive"))
    )
    (net (code "27") (name "/PA4") (class "Default")
      (node (ref "DD3") (pin "20") (pinfunction "PA4_20") (pintype "passive"))
      (node (ref "DD4") (pin "5") (pinfunction "CS_5") (pintype "passive"))
      (node (ref "R18") (pin "2") (pinfunction "2_2") (pintype "passive"))
    )
    (net (code "28") (name "/PA5") (class "Default")
      (node (ref "DD3") (pin "21") (pinfunction "PA5_21") (pintype "passive"))
      (node (ref "DD4") (pin "4") (pinfunction "SCLK_4") (pintype "passive"))
    )
    (net (code "29") (name "/PA6") (class "Default")
      (node (ref "DD3") (pin "22") (pinfunction "PA6_22") (pintype "passive"))
      (node (ref "DD4") (pin "6") (pinfunction "DOUT_6") (pintype "passive"))
    )
    (net (code "30") (name "/PA7") (class "Default")
      (node (ref "DD3") (pin "23") (pinfunction "PA7_23") (pintype "passive"))
      (node (ref "DD4") (pin "2") (pinfunction "DIN_2") (pintype "passive"))
    )
    (net (code "31") (name "/PA8") (class "Default")
      (node (ref "DD3") (pin "41") (pinfunction "PA8_41") (pintype "passive"))
      (node (ref "R2") (pin "1") (pinfunction "1_1") (pintype "passive"))
    )
    (net (code "32") (name "/PA9") (class "Default")
      (node (ref "16") (pin "1") (pinfunction "1_1") (pintype "passive"))
      (node (ref "DD3") (pin "42") (pinfunction "PA9_42") (pintype "passive"))
    )
    (net (code "33") (name "/PA10") (class "Default")
      (node (ref "15") (pin "1") (pinfunction "1_1") (pintype "passive"))
      (node (ref "DD3") (pin "43") (pinfunction "PA10_43") (pintype "passive"))
    )
    (net (code "34") (name "/PA11") (class "Default")
      (node (ref "C22") (pin "2") (pinfunction "2_2") (pintype "passive"))
      (node (ref "DD3") (pin "44") (pinfunction "PA11_44") (pintype "passive"))
      (node (ref "R12") (pin "2") (pinfunction "2_2") (pintype "passive"))
    )
    (net (code "35") (name "/PA12") (class "Default")
      (node (ref "C23") (pin "1") (pinfunction "1_1") (pintype "passive"))
      (node (ref "DD3") (pin "45") (pinfunction "PA12_45") (pintype "passive"))
      (node (ref "R13") (pin "2") (pinfunction "2_2") (pintype "passive"))
    )
    (net (code "36") (name "/PA13") (class "Default")
      (node (ref "DD3") (pin "46") (pinfunction "SWDIO/PA13_46") (pintype "passive"))
      (node (ref "XP1") (pin "4") (pinfunction "4_4") (pintype "passive"))
    )
    (net (code "37") (name "/PA14") (class "Default")
      (node (ref "DD3") (pin "49") (pinfunction "SWCLK/PA14_49") (pintype "passive"))
      (node (ref "XP1") (pin "2") (pinfunction "2_2") (pintype "passive"))
    )
    (net (code "38") (name "/PB0") (class "Default")
      (node (ref "9") (pin "1") (pinfunction "1_1") (pintype "passive"))
      (node (ref "DD3") (pin "26") (pinfunction "PB0_26") (pintype "passive"))
    )
    (net (code "39") (name "/PB1") (class "Default")
      (node (ref "10") (pin "1") (pinfunction "1_1") (pintype "passive"))
      (node (ref "DD3") (pin "27") (pinfunction "PB1_27") (pintype "passive"))
    )
    (net (code "40") (name "/PB8") (class "Default")
      (node (ref "14") (pin "1") (pinfunction "1_1") (pintype "passive"))
      (node (ref "DD3") (pin "61") (pinfunction "PB8_61") (pintype "passive"))
    )
    (net (code "41") (name "/PB9") (class "Default")
      (node (ref "13") (pin "1") (pinfunction "1_1") (pintype "passive"))
      (node (ref "DD3") (pin "62") (pinfunction "PB9_62") (pintype "passive"))
    )
    (net (code "42") (name "/PB10") (class "Default")
      (node (ref "11") (pin "1") (pinfunction "1_1") (pintype "passive"))
      (node (ref "DD3") (pin "29") (pinfunction "PB10_29") (pintype "passive"))
    )
    (net (code "43") (name "/PB11") (class "Default")
      (node (ref "12") (pin "1") (pinfunction "1_1") (pintype "passive"))
      (node (ref "DD3") (pin "30") (pinfunction "PB11_30") (pintype "passive"))
    )
    (net (code "44") (name "/PB12") (class "Default")
      (node (ref "21") (pin "1") (pinfunction "1_1") (pintype "passive"))
      (node (ref "DD3") (pin "33") (pinfunction "PB12_33") (pintype "passive"))
    )
    (net (code "45") (name "/PB13") (class "Default")
      (node (ref "20") (pin "1") (pinfunction "1_1") (pintype "passive"))
      (node (ref "DD3") (pin "34") (pinfunction "PB13_34") (pintype "passive"))
    )
    (net (code "46") (name "/PB14") (class "Default")
      (node (ref "19") (pin "1") (pinfunction "1_1") (pintype "passive"))
      (node (ref "DD3") (pin "35") (pinfunction "PB14_35") (pintype "passive"))
    )
    (net (code "47") (name "/PB15") (class "Default")
      (node (ref "18") (pin "1") (pinfunction "1_1") (pintype "passive"))
      (node (ref "DD3") (pin "36") (pinfunction "PB15_36") (pintype "passive"))
    )
    (net (code "48") (name "/PC4") (class "Default")
      (node (ref "7") (pin "1") (pinfunction "1_1") (pintype "passive"))
      (node (ref "DD3") (pin "24") (pinfunction "PC4_24") (pintype "passive"))
    )
    (net (code "49") (name "/PC5") (class "Default")
      (node (ref "8") (pin "1") (pinfunction "1_1") (pintype "passive"))
      (node (ref "DD3") (pin "25") (pinfunction "PC5_25") (pintype "passive"))
    )
    (net (code "50") (name "/PC6") (class "Default")
      (node (ref "17") (pin "1") (pinfunction "1_1") (pintype "passive"))
      (node (ref "DD3") (pin "37") (pinfunction "PC6_37") (pintype "passive"))
    )
    (net (code "51") (name "/PC7") (class "Default")
      (node (ref "C42") (pin "1") (pinfunction "1_1") (pintype "passive"))
      (node (ref "DD3") (pin "38") (pinfunction "PC7_38") (pintype "passive"))
      (node (ref "R26") (pin "2") (pinfunction "2_2") (pintype "passive"))
      (node (ref "XS2") (pin "9") (pinfunction "9_9") (pintype "passive"))
    )
    (net (code "52") (name "/PC8") (class "Default")
      (node (ref "DD3") (pin "39") (pinfunction "PC8_39") (pintype "passive"))
      (node (ref "R24") (pin "2") (pinfunction "2_2") (pintype "passive"))
      (node (ref "XS2") (pin "7") (pinfunction "7_7") (pintype "passive"))
    )
    (net (code "53") (name "/PC9") (class "Default")
      (node (ref "DD3") (pin "40") (pinfunction "PC9_40") (pintype "passive"))
      (node (ref "R25") (pin "2") (pinfunction "2_2") (pintype "passive"))
      (node (ref "XS2") (pin "8") (pinfunction "8_8") (pintype "passive"))
    )
    (net (code "54") (name "/PC10") (class "Default")
      (node (ref "DD3") (pin "51") (pinfunction "PC10_51") (pintype "passive"))
      (node (ref "R21") (pin "2") (pinfunction "2_2") (pintype "passive"))
      (node (ref "XS2") (pin "1") (pinfunction "1_1") (pintype "passive"))
    )
    (net (code "55") (name "/PC11") (class "Default")
      (node (ref "DD3") (pin "52") (pinfunction "PC11_52") (pintype "passive"))
      (node (ref "R23") (pin "2") (pinfunction "2_2") (pintype "passive"))
      (node (ref "XS2") (pin "2") (pinfunction "2_2") (pintype "passive"))
    )
    (net (code "56") (name "/PC12") (class "Default")
      (node (ref "DD3") (pin "53") (pinfunction "PC12_53") (pintype "passive"))
      (node (ref "XS2") (pin "5") (pinfunction "5_5") (pintype "passive"))
    )
    (net (code "57") (name "/PD2") (class "Default")
      (node (ref "DD3") (pin "54") (pinfunction "PD2_54") (pintype "passive"))
      (node (ref "R27") (pin "2") (pinfunction "2_2") (pintype "passive"))
      (node (ref "XS2") (pin "3") (pinfunction "3_3") (pintype "passive"))
    )
    (net (code "58") (name "/RTC") (class "Default")
      (node (ref "C11") (pin "2") (pinfunction "2_2") (pintype "passive"))
      (node (ref "DD3") (pin "2") (pinfunction "PC13-TAMPER-RTC_2") (pintype "passive"))
      (node (ref "R8") (pin "1") (pinfunction "1_1") (pintype "passive"))
      (node (ref "SB1") (pin "3") (pinfunction "3_3") (pintype "passive"))
      (node (ref "SB1") (pin "4") (pinfunction "4_4") (pintype "passive"))
    )
    (net (code "59") (name "/VBAT") (class "Default")
      (node (ref "DD3") (pin "1") (pinfunction "VBAT_1") (pintype "passive"))
      (node (ref "X3") (pin "2") (pinfunction "2_2") (pintype "passive"))
    )
    (net (code "60") (name "/VBUS_5V") (class "Default")
      (node (ref "C2") (pin "2") (pinfunction "2_2") (pintype "passive"))
      (node (ref "C36") (pin "1") (pinfunction "1_1") (pintype "passive"))
      (node (ref "C38") (pin "1") (pinfunction "1_1") (pintype "passive"))
      (node (ref "C7") (pin "1") (pinfunction "1_1") (pintype "passive"))
      (node (ref "C8") (pin "1") (pinfunction "1_1") (pintype "passive"))
      (node (ref "DD1") (pin "5") (pinfunction "Vbus_5") (pintype "power_in"))
      (node (ref "DD2") (pin "1") (pinfunction "Vbus1_1") (pintype "passive"))
      (node (ref "L1") (pin "2") (pinfunction "2_2") (pintype "passive"))
      (node (ref "L8") (pin "1") (pinfunction "1_1") (pintype "passive"))
    )
    (net (code "61") (name "/VCAP1") (class "Default")
      (node (ref "C29") (pin "1") (pinfunction "1_1") (pintype "passive"))
      (node (ref "DD3") (pin "31") (pinfunction "VCAP1_31") (pintype "passive"))
    )
    (net (code "62") (name "/VCAP2") (class "Default")
      (node (ref "C37") (pin "1") (pinfunction "1_1") (pintype "passive"))
      (node (ref "DD3") (pin "47") (pinfunction "VCAP2_47") (pintype "passive"))
    )
    (net (code "63") (name "/Vin") (class "Default")
      (node (ref "1") (pin "1") (pinfunction "1_1") (pintype "passive"))
      (node (ref "L3") (pin "1") (pinfunction "1_1") (pintype "passive"))
      (node (ref "L6") (pin "1") (pinfunction "1_1") (pintype "passive"))
    )
    (net (code "64") (name "GND") (class "Default")
      (node (ref "22") (pin "1") (pinfunction "1_1") (pintype "passive"))
      (node (ref "C10") (pin "2") (pinfunction "-_2") (pintype "passive"))
      (node (ref "C11") (pin "1") (pinfunction "1_1") (pintype "passive"))
      (node (ref "C12") (pin "1") (pinfunction "1_1") (pintype "passive"))
      (node (ref "C13") (pin "2") (pinfunction "-_2") (pintype "passive"))
      (node (ref "C14") (pin "2") (pinfunction "2_2") (pintype "passive"))
      (node (ref "C15") (pin "2") (pinfunction "2_2") (pintype "passive"))
      (node (ref "C16") (pin "2") (pinfunction "2_2") (pintype "passive"))
      (node (ref "C17") (pin "2") (pinfunction "2_2") (pintype "passive"))
      (node (ref "C18") (pin "1") (pinfunction "1_1") (pintype "passive"))
      (node (ref "C19") (pin "1") (pinfunction "1_1") (pintype "passive"))
      (node (ref "C20") (pin "1") (pinfunction "1_1") (pintype "passive"))
      (node (ref "C21") (pin "1") (pinfunction "1_1") (pintype "passive"))
      (node (ref "C22") (pin "1") (pinfunction "1_1") (pintype "passive"))
      (node (ref "C23") (pin "2") (pinfunction "2_2") (pintype "passive"))
      (node (ref "C24") (pin "2") (pinfunction "-_2") (pintype "passive"))
      (node (ref "C25") (pin "2") (pinfunction "2_2") (pintype "passive"))
      (node (ref "C26") (pin "2") (pinfunction "2_2") (pintype "passive"))
      (node (ref "C27") (pin "2") (pinfunction "2_2") (pintype "passive"))
      (node (ref "C28") (pin "2") (pinfunction "-_2") (pintype "passive"))
      (node (ref "C29") (pin "2") (pinfunction "2_2") (pintype "passive"))
      (node (ref "C3") (pin "2") (pinfunction "2_2") (pintype "passive"))
      (node (ref "C30") (pin "2") (pinfunction "2_2") (pintype "passive"))
      (node (ref "C31") (pin "2") (pinfunction "2_2") (pintype "passive"))
      (node (ref "C32") (pin "2") (pinfunction "-_2") (pintype "passive"))
      (node (ref "C33") (pin "2") (pinfunction "2_2") (pintype "passive"))
      (node (ref "C34") (pin "2") (pinfunction "2_2") (pintype "passive"))
      (node (ref "C35") (pin "2") (pinfunction "2_2") (pintype "passive"))
      (node (ref "C37") (pin "2") (pinfunction "2_2") (pintype "passive"))
      (node (ref "C39") (pin "2") (pinfunction "2_2") (pintype "passive"))
      (node (ref "C4") (pin "2") (pinfunction "2_2") (pintype "passive"))
      (node (ref "C41") (pin "2") (pinfunction "2_2") (pintype "passive"))
      (node (ref "C42") (pin "2") (pinfunction "2_2") (pintype "passive"))
      (node (ref "C43") (pin "2") (pinfunction "2_2") (pintype "passive"))
      (node (ref "C44") (pin "2") (pinfunction "2_2") (pintype "passive"))
      (node (ref "C45") (pin "2") (pinfunction "2_2") (pintype "passive"))
      (node (ref "C46") (pin "2") (pinfunction "2_2") (pintype "passive"))
      (node (ref "C47") (pin "2") (pinfunction "2_2") (pintype "passive"))
      (node (ref "C48") (pin "2") (pinfunction "2_2") (pintype "passive"))
      (node (ref "C49") (pin "2") (pinfunction "-_2") (pintype "passive"))
      (node (ref "C5") (pin "2") (pinfunction "-_2") (pintype "passive"))
      (node (ref "C50") (pin "2") (pinfunction "-_2") (pintype "passive"))
      (node (ref "C6") (pin "2") (pinfunction "-_2") (pintype "passive"))
      (node (ref "DA1") (pin "1") (pinfunction "ADJ/GND_1") (pintype "power_in"))
      (node (ref "DA2") (pin "4") (pinfunction "GND_4") (pintype "power_in"))
      (node (ref "DA3") (pin "1") (pinfunction "ADJ/GND_1") (pintype "power_in"))
      (node (ref "DA4") (pin "3") (pinfunction "-Vout_3") (pintype "passive"))
      (node (ref "DD2") (pin "15") (pinfunction "GND2_15") (pintype "passive"))
      (node (ref "DD2") (pin "9") (pinfunction "GND2_9") (pintype "passive"))
      (node (ref "DD3") (pin "12") (pinfunction "VSSA_12") (pintype "passive"))
      (node (ref "DD3") (pin "18") (pinfunction "VSS_18") (pintype "passive"))
      (node (ref "DD3") (pin "63") (pinfunction "VSS_63") (pintype "passive"))
      (node (ref "DD4") (pin "1") (pinfunction "GND_1") (pintype "passive"))
      (node (ref "DD5") (pin "4") (pinfunction "GND_4") (pintype "power_in"))
      (node (ref "E1") (pin "2") (pinfunction "2_2") (pintype "passive"))
      (node (ref "R16") (pin "2") (pinfunction "2_2") (pintype "passive"))
      (node (ref "R19") (pin "1") (pinfunction "1_1") (pintype "passive"))
      (node (ref "R22") (pin "2") (pinfunction "2_2") (pintype "passive"))
      (node (ref "R5") (pin "2") (pinfunction "2_2") (pintype "passive"))
      (node (ref "SB1") (pin "1") (pinfunction "1_1") (pintype "passive"))
      (node (ref "SB1") (pin "2") (pinfunction "2_2") (pintype "passive"))
      (node (ref "SB2") (pin "1") (pinfunction "1_1") (pintype "passive"))
      (node (ref "SB2") (pin "2") (pinfunction "2_2") (pintype "passive"))
      (node (ref "VD1") (pin "1") (pinfunction "+_1") (pintype "passive"))
      (node (ref "VD2") (pin "1") (pinfunction "+_1") (pintype "passive"))
      (node (ref "VT1") (pin "2") (pinfunction "E_2") (pintype "passive"))
      (node (ref "X1") (pin "3") (pinfunction "3_3") (pintype "passive"))
      (node (ref "XP1") (pin "3") (pinfunction "3_3") (pintype "passive"))
      (node (ref "XS2") (pin "10") (pinfunction "10_10") (pintype "passive"))
      (node (ref "XS2") (pin "6") (pinfunction "6_6") (pintype "passive"))
    )
    (net (code "65") (name "Net-(C1-Pad2)") (class "Default")
      (node (ref "C1") (pin "2") (pinfunction "2_2") (pintype "passive"))
      (node (ref "R1") (pin "2") (pinfunction "2_2") (pintype "passive"))
      (node (ref "XS1") (pin "5") (pintype "passive"))
      (node (ref "XS1") (pin "6") (pintype "passive"))
    )
    (net (code "66") (name "Net-(C5-+)") (class "Default")
      (node (ref "C3") (pin "1") (pinfunction "1_1") (pintype "passive"))
      (node (ref "C5") (pin "1") (pinfunction "+_1") (pintype "passive"))
      (node (ref "DA2") (pin "2") (pinfunction "Vin_2") (pintype "power_in"))
      (node (ref "L3") (pin "2") (pinfunction "2_2") (pintype "passive"))
    )
    (net (code "67") (name "Net-(C6-+)") (class "Default")
      (node (ref "C4") (pin "1") (pinfunction "1_1") (pintype "passive"))
      (node (ref "C6") (pin "1") (pinfunction "+_1") (pintype "passive"))
      (node (ref "DA1") (pin "3") (pinfunction "Vin_3") (pintype "power_in"))
      (node (ref "L4") (pin "2") (pinfunction "2_2") (pintype "passive"))
    )
    (net (code "68") (name "Net-(C12-Pad2)") (class "Default")
      (node (ref "C12") (pin "2") (pinfunction "2_2") (pintype "passive"))
      (node (ref "R10") (pin "2") (pinfunction "2_2") (pintype "passive"))
      (node (ref "R9") (pin "1") (pinfunction "1_1") (pintype "passive"))
      (node (ref "SB2") (pin "3") (pinfunction "3_3") (pintype "passive"))
      (node (ref "SB2") (pin "4") (pinfunction "4_4") (pintype "passive"))
    )
    (net (code "69") (name "Net-(C21-Pad2)") (class "Default")
      (node (ref "C21") (pin "2") (pinfunction "2_2") (pintype "passive"))
      (node (ref "R14") (pin "2") (pinfunction "2_2") (pintype "passive"))
      (node (ref "R17") (pin "2") (pinfunction "2_2") (pintype "passive"))
      (node (ref "ZQ2") (pin "1") (pinfunction "1_1") (pintype "passive"))
    )
    (net (code "70") (name "Net-(C24-+)") (class "Default")
      (node (ref "C24") (pin "1") (pinfunction "+_1") (pintype "passive"))
      (node (ref "C26") (pin "1") (pinfunction "1_1") (pintype "passive"))
      (node (ref "DD3") (pin "13") (pinfunction "VDDA_13") (pintype "passive"))
      (node (ref "L7") (pin "2") (pinfunction "2_2") (pintype "passive"))
    )
    (net (code "71") (name "Net-(C28-+)") (class "Default")
      (node (ref "C27") (pin "1") (pinfunction "1_1") (pintype "passive"))
      (node (ref "C28") (pin "1") (pinfunction "+_1") (pintype "passive"))
      (node (ref "DA3") (pin "3") (pinfunction "Vin_3") (pintype "power_in"))
      (node (ref "L6") (pin "2") (pinfunction "2_2") (pintype "passive"))
    )
    (net (code "72") (name "Net-(DA4-+Vin)") (class "Default")
      (node (ref "C40") (pin "1") (pinfunction "1_1") (pintype "passive"))
      (node (ref "DA4") (pin "2") (pinfunction "+Vin_2") (pintype "passive"))
      (node (ref "L8") (pin "2") (pinfunction "2_2") (pintype "passive"))
    )
    (net (code "73") (name "Net-(DA4-+Vout)") (class "Default")
      (node (ref "C43") (pin "1") (pinfunction "1_1") (pintype "passive"))
      (node (ref "DA4") (pin "4") (pinfunction "+Vout_4") (pintype "passive"))
      (node (ref "L9") (pin "1") (pinfunction "1_1") (pintype "passive"))
    )
    (net (code "74") (name "Net-(DD1-I{slash}O1-Pad1)") (class "Default")
      (node (ref "DD1") (pin "1") (pinfunction "I/O1_1") (pintype "bidirectional"))
      (node (ref "XS1") (pin "2") (pintype "passive"))
    )
    (net (code "75") (name "Net-(DD1-I{slash}O1-Pad6)") (class "Default")
      (node (ref "DD1") (pin "6") (pinfunction "I/O1_6") (pintype "bidirectional"))
      (node (ref "L5") (pin "1") (pintype "passive"))
    )
    (net (code "76") (name "Net-(DD1-I{slash}O2-Pad3)") (class "Default")
      (node (ref "DD1") (pin "3") (pinfunction "I/O2_3") (pintype "bidirectional"))
      (node (ref "XS1") (pin "3") (pintype "passive"))
    )
    (net (code "77") (name "Net-(DD1-I{slash}O2-Pad4)") (class "Default")
      (node (ref "DD1") (pin "4") (pinfunction "I/O2_4") (pintype "bidirectional"))
      (node (ref "L5") (pin "2") (pintype "passive"))
    )
    (net (code "78") (name "Net-(DD2-DD+)") (class "Default")
      (node (ref "DD2") (pin "10") (pinfunction "DD+_10") (pintype "passive"))
      (node (ref "R11") (pin "1") (pinfunction "1_1") (pintype "passive"))
      (node (ref "R13") (pin "1") (pinfunction "1_1") (pintype "passive"))
    )
    (net (code "79") (name "Net-(DD2-DD-)") (class "Default")
      (node (ref "DD2") (pin "11") (pinfunction "DD-_11") (pintype "passive"))
      (node (ref "R12") (pin "1") (pinfunction "1_1") (pintype "passive"))
    )
    (net (code "80") (name "Net-(DD2-PDEN)") (class "Default")
      (node (ref "C9") (pin "2") (pinfunction "2_2") (pintype "passive"))
      (node (ref "DD2") (pin "3") (pinfunction "Vdd1_3") (pintype "passive"))
      (node (ref "DD2") (pin "4") (pinfunction "PDEN_4") (pintype "passive"))
      (node (ref "DD2") (pin "5") (pinfunction "SPU_5") (pintype "passive"))
    )
    (net (code "81") (name "Net-(DD2-UD+)") (class "Default")
      (node (ref "DD2") (pin "7") (pinfunction "UD+_7") (pintype "passive"))
      (node (ref "R6") (pin "2") (pinfunction "2_2") (pintype "passive"))
    )
    (net (code "82") (name "Net-(DD2-UD-)") (class "Default")
      (node (ref "DD2") (pin "6") (pinfunction "UD-_6") (pintype "passive"))
      (node (ref "R4") (pin "2") (pinfunction "2_2") (pintype "passive"))
    )
    (net (code "83") (name "Net-(E1-Pad1)") (class "Default")
      (node (ref "E1") (pin "1") (pinfunction "1_1") (pintype "passive"))
      (node (ref "X3") (pin "1") (pinfunction "1_1") (pintype "passive"))
    )
    (net (code "84") (name "Net-(HL1--)") (class "Default")
      (node (ref "HL1") (pin "2") (pinfunction "-_2") (pintype "passive"))
      (node (ref "R28") (pin "2") (pinfunction "2_2") (pintype "passive"))
    )
    (net (code "85") (name "Net-(HL2--)") (class "Default")
      (node (ref "HL2") (pin "2") (pinfunction "-_2") (pintype "passive"))
      (node (ref "R29") (pin "2") (pinfunction "2_2") (pintype "passive"))
    )
    (net (code "86") (name "Net-(HL3--)") (class "Default")
      (node (ref "HL3") (pin "2") (pinfunction "-_2") (pintype "passive"))
      (node (ref "R30") (pin "2") (pinfunction "2_2") (pintype "passive"))
    )
    (net (code "87") (name "Net-(L1-Pad1)") (class "Default")
      (node (ref "L1") (pin "1") (pinfunction "1_1") (pintype "passive"))
      (node (ref "XS1") (pin "1") (pintype "passive"))
    )
    (net (code "88") (name "Net-(L2-Pad1)") (class "Default")
      (node (ref "L2") (pin "1") (pinfunction "1_1") (pintype "passive"))
      (node (ref "XS1") (pin "4") (pintype "passive"))
    )
    (net (code "89") (name "Net-(L5-Pad3)") (class "Default")
      (node (ref "L5") (pin "3") (pintype "passive"))
      (node (ref "R6") (pin "1") (pinfunction "1_1") (pintype "passive"))
    )
    (net (code "90") (name "Net-(L5-Pad4)") (class "Default")
      (node (ref "L5") (pin "4") (pintype "passive"))
      (node (ref "R4") (pin "1") (pinfunction "1_1") (pintype "passive"))
    )
    (net (code "91") (name "Net-(R2-Pad2)") (class "Default")
      (node (ref "R2") (pin "2") (pinfunction "2_2") (pintype "passive"))
      (node (ref "X1") (pin "1") (pinfunction "1_1") (pintype "passive"))
    )
    (net (code "92") (name "Net-(R15-Pad1)") (class "Default")
      (node (ref "R15") (pin "1") (pinfunction "1_1") (pintype "passive"))
      (node (ref "X2") (pin "1") (pinfunction "1_1") (pintype "passive"))
    )
    (net (code "93") (name "Net-(R20-Pad2)") (class "Default")
      (node (ref "R20") (pin "2") (pinfunction "2_2") (pintype "passive"))
      (node (ref "X4") (pin "1") (pinfunction "1_1") (pintype "passive"))
    )
    (net (code "94") (name "Net-(VT1-B)") (class "Default")
      (node (ref "R3") (pin "1") (pinfunction "1_1") (pintype "passive"))
      (node (ref "VT1") (pin "1") (pinfunction "B_1") (pintype "passive"))
      (node (ref "X1") (pin "2") (pinfunction "2_2") (pintype "passive"))
    )
    (net (code "95") (name "Net-(VT1-K)") (class "Default")
      (node (ref "R5") (pin "1") (pinfunction "1_1") (pintype "passive"))
      (node (ref "R7") (pin "1") (pinfunction "1_1") (pintype "passive"))
      (node (ref "VT1") (pin "3") (pinfunction "K_3") (pintype "passive"))
      (node (ref "VT2") (pin "1") (pinfunction "B_1") (pintype "passive"))
    )
    (net (code "96") (name "Net-(VT2-E)") (class "Default")
      (node (ref "R11") (pin "2") (pinfunction "2_2") (pintype "passive"))
      (node (ref "VT2") (pin "2") (pinfunction "E_2") (pintype "passive"))
    )
    (net (code "97") (name "unconnected-(DA2-NC-Pad1)") (class "Default")
      (node (ref "DA2") (pin "1") (pinfunction "NC_1") (pintype "passive"))
    )
    (net (code "98") (name "unconnected-(DA2-NC-Pad3)") (class "Default")
      (node (ref "DA2") (pin "3") (pinfunction "NC_3") (pintype "passive"))
    )
    (net (code "99") (name "unconnected-(DA2-NC-Pad5)") (class "Default")
      (node (ref "DA2") (pin "5") (pinfunction "NC_5") (pintype "passive"))
    )
    (net (code "100") (name "unconnected-(DA2-NC-Pad7)") (class "Default")
      (node (ref "DA2") (pin "7") (pinfunction "NC_7") (pintype "passive"))
    )
    (net (code "101") (name "unconnected-(DA2-TP-Pad8)") (class "Default")
      (node (ref "DA2") (pin "8") (pinfunction "TP_8") (pintype "passive"))
    )
  )
)
